# RS485_Com_and_Connectors.net
KiCad netlist of a schematic drawn in Altium Designer
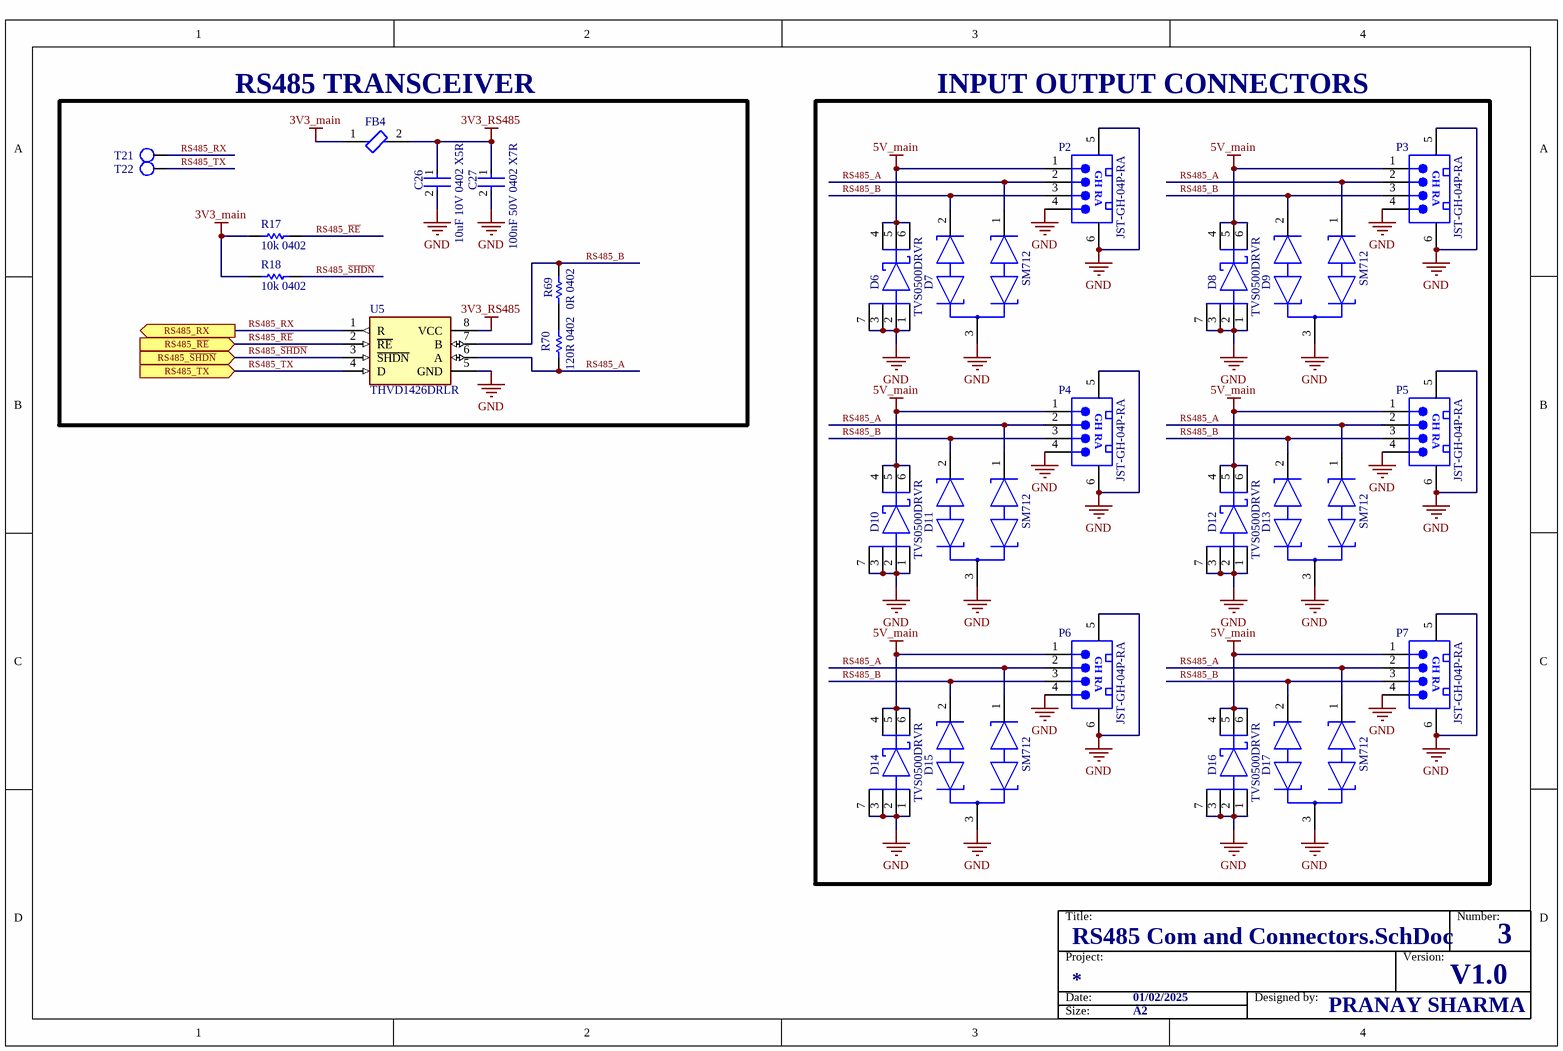
[diagram p0: RS485 Com and Connectors.SchDoc]

(export (version "E")
  (design (tool "Eeschema 10.0.6"))
  (components
    (comp (ref "C26")
      (value "10uF 10V 0402 X5R")
      (footprint "Res, Cap, Ind, LED, FB_Lib:0402 IPC CLASS C CAPACITOR")
      (libsource (lib "Capacitor_Lib") (part "10uF 10V 0402 X5R"))
    )
    (comp (ref "C27")
      (value "100nF 50V 0402 X7R")
      (footprint "Res, Cap, Ind, LED, FB_Lib:0402 IPC CLASS C CAPACITOR")
      (libsource (lib "Capacitor_Lib") (part "100nF 50V 0402 X7R"))
    )
    (comp (ref "D6")
      (value "TVS0500DRVR")
      (footprint "Res, Cap, Ind, LED, FB_Lib:DRV0006A IPC-C")
      (libsource (lib "Diodes_Lib") (part "TVS0500DRVR"))
    )
    (comp (ref "D7")
      (value "SM712")
      (footprint "Res, Cap, Ind, LED, FB_Lib:FP-SOT23-IPC_C")
      (libsource (lib "Diodes_Lib") (part "SM712"))
    )
    (comp (ref "D8")
      (value "TVS0500DRVR")
      (footprint "Res, Cap, Ind, LED, FB_Lib:DRV0006A IPC-C")
      (libsource (lib "Diodes_Lib") (part "TVS0500DRVR"))
    )
    (comp (ref "D9")
      (value "SM712")
      (footprint "Res, Cap, Ind, LED, FB_Lib:FP-SOT23-IPC_C")
      (libsource (lib "Diodes_Lib") (part "SM712"))
    )
    (comp (ref "D10")
      (value "TVS0500DRVR")
      (footprint "Res, Cap, Ind, LED, FB_Lib:DRV0006A IPC-C")
      (libsource (lib "Diodes_Lib") (part "TVS0500DRVR"))
    )
    (comp (ref "D11")
      (value "SM712")
      (footprint "Res, Cap, Ind, LED, FB_Lib:FP-SOT23-IPC_C")
      (libsource (lib "Diodes_Lib") (part "SM712"))
    )
    (comp (ref "D12")
      (value "TVS0500DRVR")
      (footprint "Res, Cap, Ind, LED, FB_Lib:DRV0006A IPC-C")
      (libsource (lib "Diodes_Lib") (part "TVS0500DRVR"))
    )
    (comp (ref "D13")
      (value "SM712")
      (footprint "Res, Cap, Ind, LED, FB_Lib:FP-SOT23-IPC_C")
      (libsource (lib "Diodes_Lib") (part "SM712"))
    )
    (comp (ref "D14")
      (value "TVS0500DRVR")
      (footprint "Res, Cap, Ind, LED, FB_Lib:DRV0006A IPC-C")
      (libsource (lib "Diodes_Lib") (part "TVS0500DRVR"))
    )
    (comp (ref "D15")
      (value "SM712")
      (footprint "Res, Cap, Ind, LED, FB_Lib:FP-SOT23-IPC_C")
      (libsource (lib "Diodes_Lib") (part "SM712"))
    )
    (comp (ref "D16")
      (value "TVS0500DRVR")
      (footprint "Res, Cap, Ind, LED, FB_Lib:DRV0006A IPC-C")
      (libsource (lib "Diodes_Lib") (part "TVS0500DRVR"))
    )
    (comp (ref "D17")
      (value "SM712")
      (footprint "Res, Cap, Ind, LED, FB_Lib:FP-SOT23-IPC_C")
      (libsource (lib "Diodes_Lib") (part "SM712"))
    )
    (comp (ref "FB4")
      (value "BLM15AX102SN1D")
      (footprint "Res, Cap, Ind, LED, FB_Lib:0402 IPC CLASS C FERRITE BEAD")
      (libsource (lib "Ferrite_Bead_Lib") (part "BLM15AX102SN1D"))
    )
    (comp (ref "P2")
      (value "JST-GH-04P-RA")
      (footprint "Connectors_Lib:JST-GH-04P-RA")
      (libsource (lib "Connectors_Lib") (part "JST-GH-04P-RA"))
    )
    (comp (ref "P3")
      (value "JST-GH-04P-RA")
      (footprint "Connectors_Lib:JST-GH-04P-RA")
      (libsource (lib "Connectors_Lib") (part "JST-GH-04P-RA"))
    )
    (comp (ref "P4")
      (value "JST-GH-04P-RA")
      (footprint "Connectors_Lib:JST-GH-04P-RA")
      (libsource (lib "Connectors_Lib") (part "JST-GH-04P-RA"))
    )
    (comp (ref "P5")
      (value "JST-GH-04P-RA")
      (footprint "Connectors_Lib:JST-GH-04P-RA")
      (libsource (lib "Connectors_Lib") (part "JST-GH-04P-RA"))
    )
    (comp (ref "P6")
      (value "JST-GH-04P-RA")
      (footprint "Connectors_Lib:JST-GH-04P-RA")
      (libsource (lib "Connectors_Lib") (part "JST-GH-04P-RA"))
    )
    (comp (ref "P7")
      (value "JST-GH-04P-RA")
      (footprint "Connectors_Lib:JST-GH-04P-RA")
      (libsource (lib "Connectors_Lib") (part "JST-GH-04P-RA"))
    )
    (comp (ref "R17")
      (value "10k 0402")
      (footprint "Res, Cap, Ind, LED, FB_Lib:0402 IPC CLASS C RESISTOR")
      (libsource (lib "Resistor_Lib") (part "10k 1% 0402"))
    )
    (comp (ref "R18")
      (value "10k 0402")
      (footprint "Res, Cap, Ind, LED, FB_Lib:0402 IPC CLASS C RESISTOR")
      (libsource (lib "Resistor_Lib") (part "10k 1% 0402"))
    )
    (comp (ref "R69")
      (value "0R 0402")
      (footprint "Res, Cap, Ind, LED, FB_Lib:0402 IPC CLASS B RESISTOR")
      (libsource (lib "Resistor_Lib") (part "0R 1% 0402"))
    )
    (comp (ref "R70")
      (value "120R 0402")
      (footprint "Res, Cap, Ind, LED, FB_Lib:0402 IPC CLASS C RESISTOR")
      (libsource (lib "Resistor_Lib") (part "120R 1% 0402"))
    )
    (comp (ref "T21")
      (value "TP")
      (footprint "Miscellaneous_Lib:Testpoint1")
      (libsource (lib "Miscellaneous_Lib") (part "Testpoint1"))
    )
    (comp (ref "T22")
      (value "TP")
      (footprint "Miscellaneous_Lib:Testpoint1")
      (libsource (lib "Miscellaneous_Lib") (part "Testpoint1"))
    )
    (comp (ref "U5")
      (value "THVD1426DRLR")
      (footprint "Integrated_Circuits_Lib:DRL0008A IPC-C")
      (libsource (lib "Integrated_Circuits_Lib") (part "THVD1426DRLR"))
    )
  )
  (nets
    (net (code "1") (name "/RS485_A") (class "Default")
      (node (ref "D11") (pin "1") (pinfunction "K1_1") (pintype "passive"))
      (node (ref "D13") (pin "1") (pinfunction "K1_1") (pintype "passive"))
      (node (ref "D15") (pin "1") (pinfunction "K1_1") (pintype "passive"))
      (node (ref "D17") (pin "1") (pinfunction "K1_1") (pintype "passive"))
      (node (ref "D7") (pin "1") (pinfunction "K1_1") (pintype "passive"))
      (node (ref "D9") (pin "1") (pinfunction "K1_1") (pintype "passive"))
      (node (ref "P2") (pin "2") (pinfunction "2_2") (pintype "passive"))
      (node (ref "P3") (pin "2") (pinfunction "2_2") (pintype "passive"))
      (node (ref "P4") (pin "2") (pinfunction "2_2") (pintype "passive"))
      (node (ref "P5") (pin "2") (pinfunction "2_2") (pintype "passive"))
      (node (ref "P6") (pin "2") (pinfunction "2_2") (pintype "passive"))
      (node (ref "P7") (pin "2") (pinfunction "2_2") (pintype "passive"))
      (node (ref "R70") (pin "1") (pinfunction "1_1") (pintype "passive"))
      (node (ref "U5") (pin "6") (pinfunction "A_6") (pintype "bidirectional"))
    )
    (net (code "2") (name "/RS485_B") (class "Default")
      (node (ref "D11") (pin "2") (pinfunction "K2_2") (pintype "passive"))
      (node (ref "D13") (pin "2") (pinfunction "K2_2") (pintype "passive"))
      (node (ref "D15") (pin "2") (pinfunction "K2_2") (pintype "passive"))
      (node (ref "D17") (pin "2") (pinfunction "K2_2") (pintype "passive"))
      (node (ref "D7") (pin "2") (pinfunction "K2_2") (pintype "passive"))
      (node (ref "D9") (pin "2") (pinfunction "K2_2") (pintype "passive"))
      (node (ref "P2") (pin "3") (pinfunction "3_3") (pintype "passive"))
      (node (ref "P3") (pin "3") (pinfunction "3_3") (pintype "passive"))
      (node (ref "P4") (pin "3") (pinfunction "3_3") (pintype "passive"))
      (node (ref "P5") (pin "3") (pinfunction "3_3") (pintype "passive"))
      (node (ref "P6") (pin "3") (pinfunction "3_3") (pintype "passive"))
      (node (ref "P7") (pin "3") (pinfunction "3_3") (pintype "passive"))
      (node (ref "R69") (pin "2") (pinfunction "2_2") (pintype "passive"))
      (node (ref "U5") (pin "7") (pinfunction "B_7") (pintype "bidirectional"))
    )
    (net (code "3") (name "/RS485_RX") (class "Default")
      (node (ref "T21") (pin "0") (pinfunction "0_0") (pintype "passive"))
      (node (ref "U5") (pin "1") (pinfunction "R_1") (pintype "output"))
    )
    (net (code "4") (name "/RS485_TX") (class "Default")
      (node (ref "T22") (pin "0") (pinfunction "0_0") (pintype "passive"))
      (node (ref "U5") (pin "4") (pinfunction "D_4") (pintype "input"))
    )
    (net (code "5") (name "/RS485_~{RE}") (class "Default")
      (node (ref "R17") (pin "1") (pinfunction "1_1") (pintype "passive"))
      (node (ref "U5") (pin "2") (pinfunction "~{RE}_2") (pintype "input"))
    )
    (net (code "6") (name "/RS485_~{SHDN}") (class "Default")
      (node (ref "R18") (pin "1") (pinfunction "1_1") (pintype "passive"))
      (node (ref "U5") (pin "3") (pinfunction "~{SHDN}_3") (pintype "input"))
    )
    (net (code "7") (name "3V3_RS485") (class "Default")
      (node (ref "C26") (pin "1") (pinfunction "1_1") (pintype "passive"))
      (node (ref "C27") (pin "1") (pinfunction "1_1") (pintype "passive"))
      (node (ref "FB4") (pin "2") (pinfunction "2_2") (pintype "passive"))
      (node (ref "U5") (pin "8") (pinfunction "VCC_8") (pintype "power_in"))
    )
    (net (code "8") (name "3V3_main") (class "Default")
      (node (ref "FB4") (pin "1") (pinfunction "1_1") (pintype "passive"))
      (node (ref "R17") (pin "2") (pinfunction "2_2") (pintype "passive"))
      (node (ref "R18") (pin "2") (pinfunction "2_2") (pintype "passive"))
    )
    (net (code "9") (name "5V_main") (class "Default")
      (node (ref "D10") (pin "4") (pinfunction "4_4") (pintype "passive"))
      (node (ref "D10") (pin "5") (pinfunction "5_5") (pintype "passive"))
      (node (ref "D10") (pin "6") (pinfunction "6_6") (pintype "passive"))
      (node (ref "D12") (pin "4") (pinfunction "4_4") (pintype "passive"))
      (node (ref "D12") (pin "5") (pinfunction "5_5") (pintype "passive"))
      (node (ref "D12") (pin "6") (pinfunction "6_6") (pintype "passive"))
      (node (ref "D14") (pin "4") (pinfunction "4_4") (pintype "passive"))
      (node (ref "D14") (pin "5") (pinfunction "5_5") (pintype "passive"))
      (node (ref "D14") (pin "6") (pinfunction "6_6") (pintype "passive"))
      (node (ref "D16") (pin "4") (pinfunction "4_4") (pintype "passive"))
      (node (ref "D16") (pin "5") (pinfunction "5_5") (pintype "passive"))
      (node (ref "D16") (pin "6") (pinfunction "6_6") (pintype "passive"))
      (node (ref "D6") (pin "4") (pinfunction "4_4") (pintype "passive"))
      (node (ref "D6") (pin "5") (pinfunction "5_5") (pintype "passive"))
      (node (ref "D6") (pin "6") (pinfunction "6_6") (pintype "passive"))
      (node (ref "D8") (pin "4") (pinfunction "4_4") (pintype "passive"))
      (node (ref "D8") (pin "5") (pinfunction "5_5") (pintype "passive"))
      (node (ref "D8") (pin "6") (pinfunction "6_6") (pintype "passive"))
      (node (ref "P2") (pin "1") (pinfunction "1_1") (pintype "passive"))
      (node (ref "P3") (pin "1") (pinfunction "1_1") (pintype "passive"))
      (node (ref "P4") (pin "1") (pinfunction "1_1") (pintype "passive"))
      (node (ref "P5") (pin "1") (pinfunction "1_1") (pintype "passive"))
      (node (ref "P6") (pin "1") (pinfunction "1_1") (pintype "passive"))
      (node (ref "P7") (pin "1") (pinfunction "1_1") (pintype "passive"))
    )
    (net (code "10") (name "GND") (class "Default")
      (node (ref "C26") (pin "2") (pinfunction "2_2") (pintype "passive"))
      (node (ref "C27") (pin "2") (pinfunction "2_2") (pintype "passive"))
      (node (ref "D10") (pin "1") (pinfunction "C_1") (pintype "passive"))
      (node (ref "D10") (pin "2") (pinfunction "A_2") (pintype "passive"))
      (node (ref "D10") (pin "3") (pinfunction "3_3") (pintype "passive"))
      (node (ref "D10") (pin "7") (pinfunction "7_7") (pintype "passive"))
      (node (ref "D11") (pin "3") (pinfunction "CC_3") (pintype "passive"))
      (node (ref "D12") (pin "1") (pinfunction "C_1") (pintype "passive"))
      (node (ref "D12") (pin "2") (pinfunction "A_2") (pintype "passive"))
      (node (ref "D12") (pin "3") (pinfunction "3_3") (pintype "passive"))
      (node (ref "D12") (pin "7") (pinfunction "7_7") (pintype "passive"))
      (node (ref "D13") (pin "3") (pinfunction "CC_3") (pintype "passive"))
      (node (ref "D14") (pin "1") (pinfunction "C_1") (pintype "passive"))
      (node (ref "D14") (pin "2") (pinfunction "A_2") (pintype "passive"))
      (node (ref "D14") (pin "3") (pinfunction "3_3") (pintype "passive"))
      (node (ref "D14") (pin "7") (pinfunction "7_7") (pintype "passive"))
      (node (ref "D15") (pin "3") (pinfunction "CC_3") (pintype "passive"))
      (node (ref "D16") (pin "1") (pinfunction "C_1") (pintype "passive"))
      (node (ref "D16") (pin "2") (pinfunction "A_2") (pintype "passive"))
      (node (ref "D16") (pin "3") (pinfunction "3_3") (pintype "passive"))
      (node (ref "D16") (pin "7") (pinfunction "7_7") (pintype "passive"))
      (node (ref "D17") (pin "3") (pinfunction "CC_3") (pintype "passive"))
      (node (ref "D6") (pin "1") (pinfunction "C_1") (pintype "passive"))
      (node (ref "D6") (pin "2") (pinfunction "A_2") (pintype "passive"))
      (node (ref "D6") (pin "3") (pinfunction "3_3") (pintype "passive"))
      (node (ref "D6") (pin "7") (pinfunction "7_7") (pintype "passive"))
      (node (ref "D7") (pin "3") (pinfunction "CC_3") (pintype "passive"))
      (node (ref "D8") (pin "1") (pinfunction "C_1") (pintype "passive"))
      (node (ref "D8") (pin "2") (pinfunction "A_2") (pintype "passive"))
      (node (ref "D8") (pin "3") (pinfunction "3_3") (pintype "passive"))
      (node (ref "D8") (pin "7") (pinfunction "7_7") (pintype "passive"))
      (node (ref "D9") (pin "3") (pinfunction "CC_3") (pintype "passive"))
      (node (ref "P2") (pin "4") (pinfunction "4_4") (pintype "passive"))
      (node (ref "P2") (pin "5") (pinfunction "5_5") (pintype "passive"))
      (node (ref "P2") (pin "6") (pinfunction "6_6") (pintype "passive"))
      (node (ref "P3") (pin "4") (pinfunction "4_4") (pintype "passive"))
      (node (ref "P3") (pin "5") (pinfunction "5_5") (pintype "passive"))
      (node (ref "P3") (pin "6") (pinfunction "6_6") (pintype "passive"))
      (node (ref "P4") (pin "4") (pinfunction "4_4") (pintype "passive"))
      (node (ref "P4") (pin "5") (pinfunction "5_5") (pintype "passive"))
      (node (ref "P4") (pin "6") (pinfunction "6_6") (pintype "passive"))
      (node (ref "P5") (pin "4") (pinfunction "4_4") (pintype "passive"))
      (node (ref "P5") (pin "5") (pinfunction "5_5") (pintype "passive"))
      (node (ref "P5") (pin "6") (pinfunction "6_6") (pintype "passive"))
      (node (ref "P6") (pin "4") (pinfunction "4_4") (pintype "passive"))
      (node (ref "P6") (pin "5") (pinfunction "5_5") (pintype "passive"))
      (node (ref "P6") (pin "6") (pinfunction "6_6") (pintype "passive"))
      (node (ref "P7") (pin "4") (pinfunction "4_4") (pintype "passive"))
      (node (ref "P7") (pin "5") (pinfunction "5_5") (pintype "passive"))
      (node (ref "P7") (pin "6") (pinfunction "6_6") (pintype "passive"))
      (node (ref "U5") (pin "5") (pinfunction "GND_5") (pintype "power_in"))
    )
    (net (code "11") (name "Net-(R69-Pad1)") (class "Default")
      (node (ref "R69") (pin "1") (pinfunction "1_1") (pintype "passive"))
      (node (ref "R70") (pin "2") (pinfunction "2_2") (pintype "passive"))
    )
  )
)
